# Two-Buttons.net
KiCad netlist of a schematic drawn in EAGLE
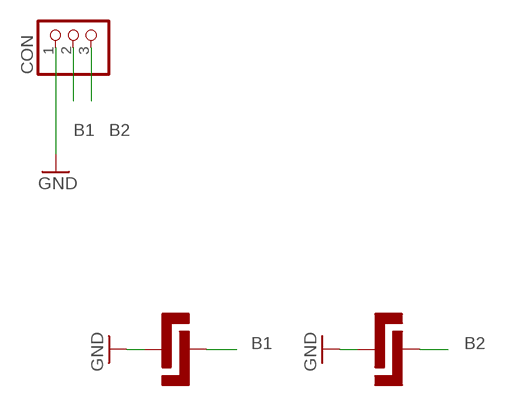
[diagram p0: schematic, sheet 1]

(export (version "E")
  (design (tool "Eeschema 10.0.6"))
  (components
    (comp (ref "BTN1")
      (value "BTN_5MM_LONG")
      (footprint "eagle-import:BTN_5MM_LONG")
      (libsource (lib "eagle-import") (part "BTN_5MM_LONG"))
    )
    (comp (ref "BTN2")
      (value "BTN_5MM_LONG")
      (footprint "eagle-import:BTN_5MM_LONG")
      (libsource (lib "eagle-import") (part "BTN_5MM_LONG"))
    )
    (comp (ref "CON")
      (value "PINHD-1X3")
      (footprint "eagle-import:1X03")
      (libsource (lib "eagle-import") (part "PINHD-1X3"))
    )
  )
  (nets
    (net (code "1") (name "/B1") (class "Default")
      (node (ref "BTN1") (pin "P$1") (pinfunction "P$1_P$1") (pintype "bidirectional"))
      (node (ref "CON") (pin "2") (pinfunction "2_2") (pintype "passive"))
    )
    (net (code "2") (name "/B2") (class "Default")
      (node (ref "BTN2") (pin "P$1") (pinfunction "P$1_P$1") (pintype "bidirectional"))
      (node (ref "CON") (pin "3") (pinfunction "3_3") (pintype "passive"))
    )
    (net (code "3") (name "GND") (class "Default")
      (node (ref "BTN1") (pin "P$2") (pinfunction "P$2_P$2") (pintype "bidirectional"))
      (node (ref "BTN2") (pin "P$2") (pinfunction "P$2_P$2") (pintype "bidirectional"))
      (node (ref "CON") (pin "1") (pinfunction "1_1") (pintype "passive"))
    )
  )
)
